# circuit_simplified.net
KiCad netlist of a schematic drawn in EAGLE
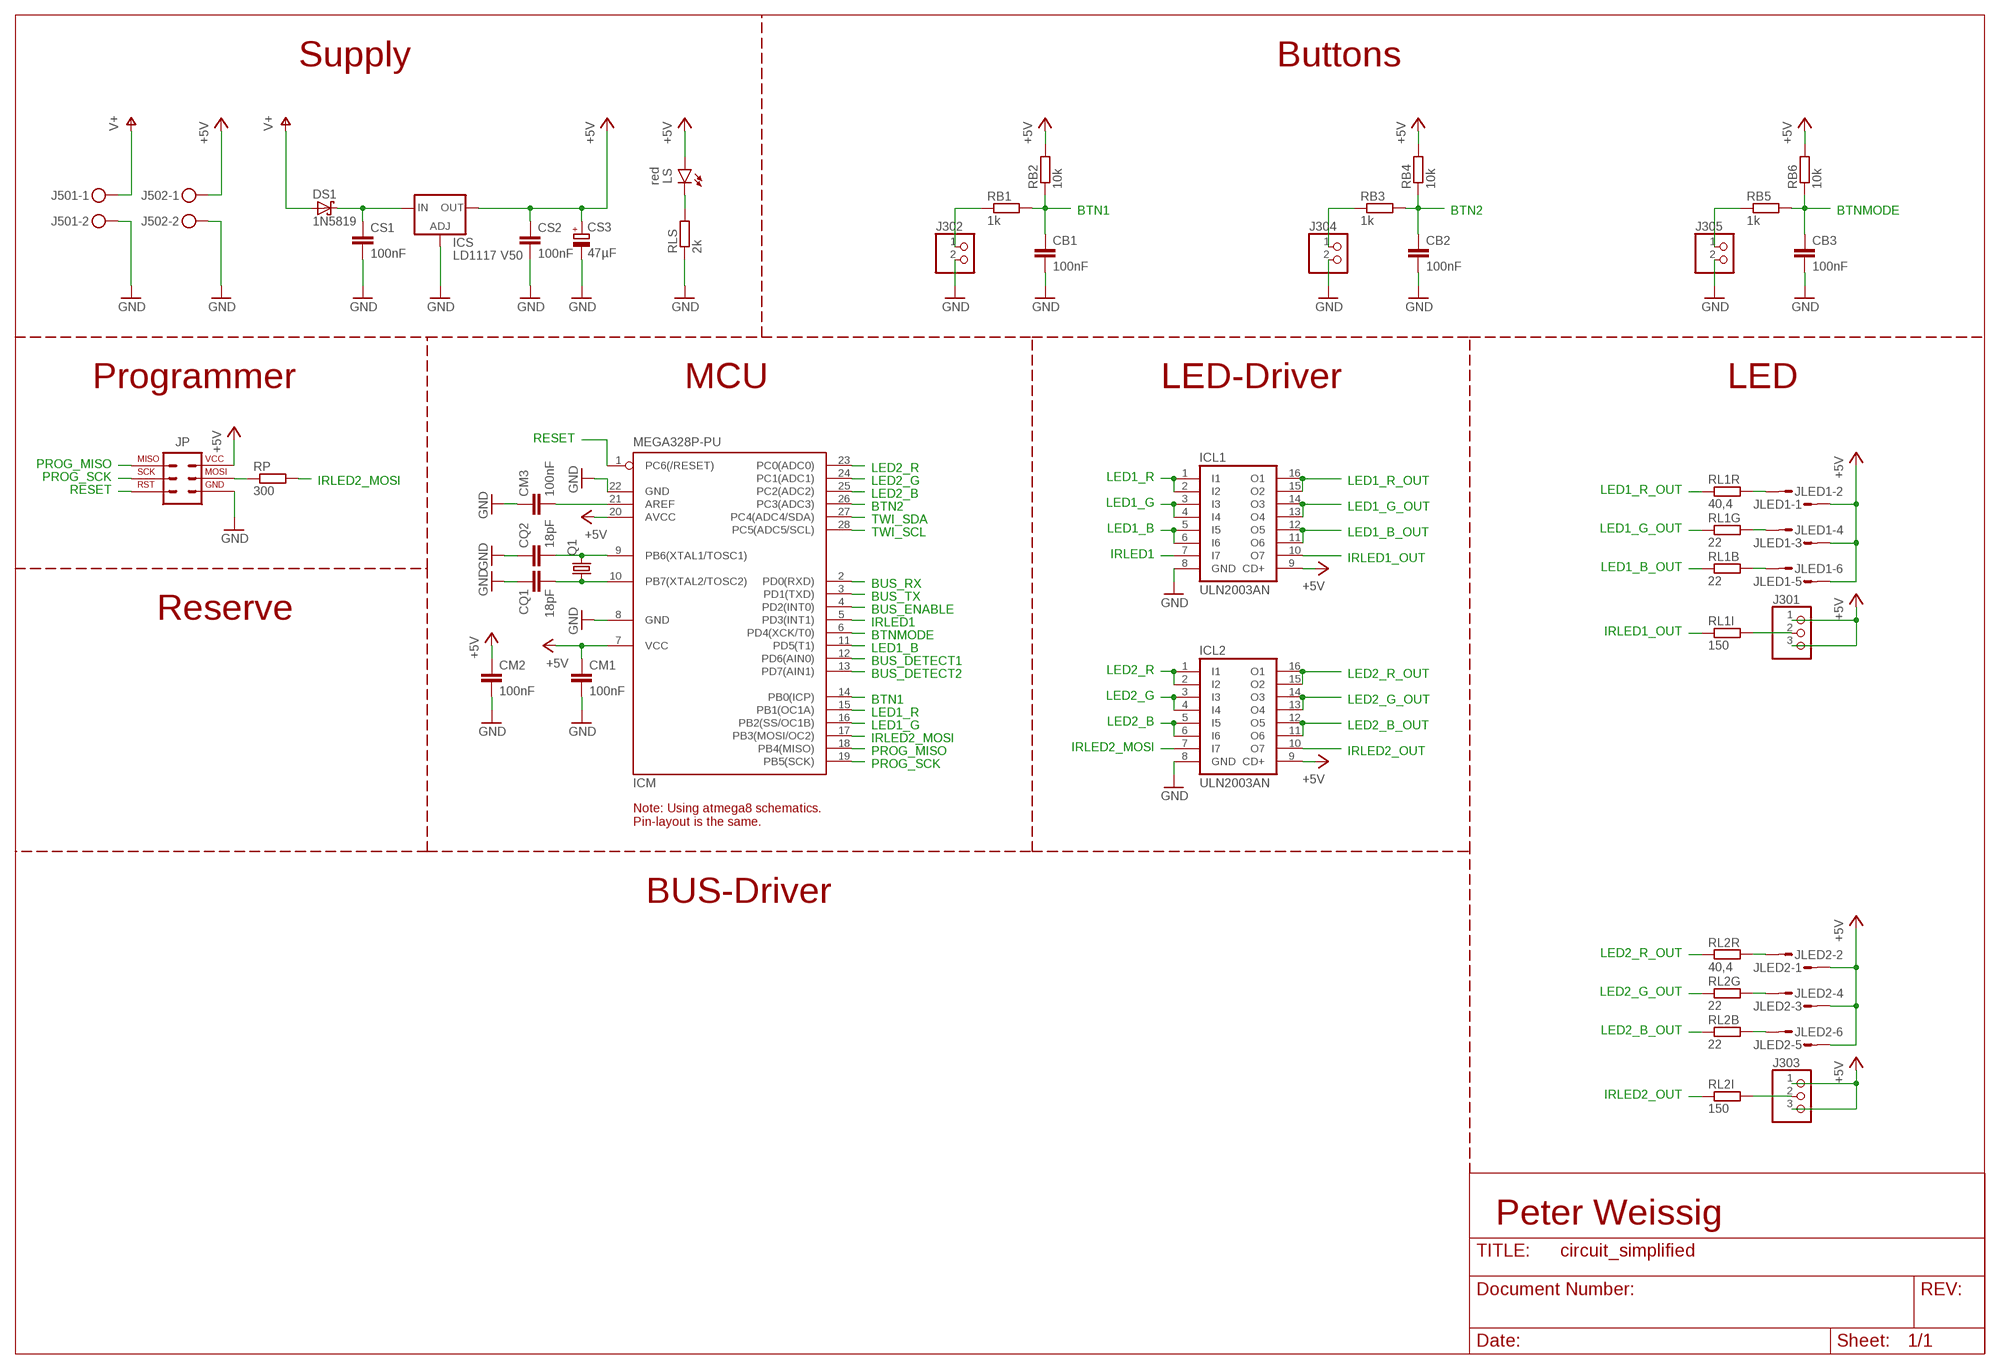
[diagram p0: schematic, sheet 1]

(export (version "E")
  (design (tool "Eeschema 10.0.6"))
  (components
    (comp (ref "CB1")
      (value "100nF")
      (footprint "eagle-import:C025-025X050")
      (libsource (lib "eagle-import") (part "C-EU025-025X050"))
    )
    (comp (ref "CB2")
      (value "100nF")
      (footprint "eagle-import:C025-025X050")
      (libsource (lib "eagle-import") (part "C-EU025-025X050"))
    )
    (comp (ref "CB3")
      (value "100nF")
      (footprint "eagle-import:C025-025X050")
      (libsource (lib "eagle-import") (part "C-EU025-025X050"))
    )
    (comp (ref "CM1")
      (value "100nF")
      (footprint "eagle-import:C025-025X050")
      (libsource (lib "eagle-import") (part "C-EU025-025X050"))
    )
    (comp (ref "CM2")
      (value "100nF")
      (footprint "eagle-import:C025-025X050")
      (libsource (lib "eagle-import") (part "C-EU025-025X050"))
    )
    (comp (ref "CM3")
      (value "100nF")
      (footprint "eagle-import:C025-025X050")
      (libsource (lib "eagle-import") (part "C-EU025-025X050"))
    )
    (comp (ref "CQ1")
      (value "18pF")
      (footprint "eagle-import:C025-025X050")
      (libsource (lib "eagle-import") (part "C-EU025-025X050"))
    )
    (comp (ref "CQ2")
      (value "18pF")
      (footprint "eagle-import:C025-025X050")
      (libsource (lib "eagle-import") (part "C-EU025-025X050"))
    )
    (comp (ref "CS1")
      (value "100nF")
      (footprint "eagle-import:C025-025X050")
      (libsource (lib "eagle-import") (part "C-EU025-025X050"))
    )
    (comp (ref "CS2")
      (value "100nF")
      (footprint "eagle-import:C025-025X050")
      (libsource (lib "eagle-import") (part "C-EU025-025X050"))
    )
    (comp (ref "CS3")
      (value "47µF")
      (footprint "eagle-import:E2-5")
      (libsource (lib "eagle-import") (part "CPOL-EUE2-5"))
    )
    (comp (ref "DS1")
      (value "1N5819")
      (footprint "eagle-import:DO41-7.6")
      (libsource (lib "eagle-import") (part "1N5819-B"))
    )
    (comp (ref "ICL1")
      (value "ULN2003AN")
      (footprint "eagle-import:DIL16")
      (libsource (lib "eagle-import") (part "ULN2003AN"))
    )
    (comp (ref "ICL2")
      (value "ULN2003AN")
      (footprint "eagle-import:DIL16")
      (libsource (lib "eagle-import") (part "ULN2003AN"))
    )
    (comp (ref "ICM")
      (value "MEGA328P-PU")
      (footprint "eagle-import:DIL28-3")
      (libsource (lib "eagle-import") (part "MEGA8-P"))
    )
    (comp (ref "ICS")
      (value "LD1117 V50")
      (footprint "eagle-import:TO220L1")
      (libsource (lib "eagle-import") (part "LD117A?V50"))
    )
    (comp (ref "J301")
      (value "PINHD-1X3")
      (footprint "eagle-import:1X03")
      (libsource (lib "eagle-import") (part "PINHD-1X3"))
    )
    (comp (ref "J302")
      (value "PINHD-1X2")
      (footprint "eagle-import:1X02")
      (libsource (lib "eagle-import") (part "PINHD-1X2"))
    )
    (comp (ref "J303")
      (value "PINHD-1X3")
      (footprint "eagle-import:1X03")
      (libsource (lib "eagle-import") (part "PINHD-1X3"))
    )
    (comp (ref "J304")
      (value "PINHD-1X2")
      (footprint "eagle-import:1X02")
      (libsource (lib "eagle-import") (part "PINHD-1X2"))
    )
    (comp (ref "J305")
      (value "PINHD-1X2")
      (footprint "eagle-import:1X02")
      (libsource (lib "eagle-import") (part "PINHD-1X2"))
    )
    (comp (ref "J501")
      (value "STECKER_SPG_2")
      (footprint "eagle-import:STECKER_SPG_2")
      (libsource (lib "eagle-import") (part "STECKER_SPG_2"))
    )
    (comp (ref "J502")
      (value "STECKER_SPG_2")
      (footprint "eagle-import:STECKER_SPG_2")
      (libsource (lib "eagle-import") (part "STECKER_SPG_2"))
    )
    (comp (ref "JLED1")
      (value "MICROMATCH-6")
      (footprint "eagle-import:MICROMATCH-6")
      (fields (field (name "MPN") "7-215464-6"))
      (libsource (lib "eagle-import") (part "MICROMATCH-6"))
    )
    (comp (ref "JLED2")
      (value "MICROMATCH-6")
      (footprint "eagle-import:MICROMATCH-6")
      (fields (field (name "MPN") "7-215464-6"))
      (libsource (lib "eagle-import") (part "MICROMATCH-6"))
    )
    (comp (ref "JP")
      (value "STECKER_ISP_6")
      (footprint "eagle-import:STECKER_WANNE_6")
      (libsource (lib "eagle-import") (part "STECKER_ISP_6"))
    )
    (comp (ref "LS")
      (value "red")
      (footprint "eagle-import:LED_3MM")
      (libsource (lib "eagle-import") (part "LED-3MM"))
    )
    (comp (ref "Q1")
      (value "CRYSTALHC49U70")
      (footprint "eagle-import:HC49U70")
      (libsource (lib "eagle-import") (part "CRYSTALHC49U70"))
    )
    (comp (ref "RB1")
      (value "1k")
      (footprint "eagle-import:0207_10")
      (libsource (lib "eagle-import") (part "R-EU_0207/10"))
    )
    (comp (ref "RB2")
      (value "10k")
      (footprint "eagle-import:0207_10")
      (libsource (lib "eagle-import") (part "R-EU_0207/10"))
    )
    (comp (ref "RB3")
      (value "1k")
      (footprint "eagle-import:0207_10")
      (libsource (lib "eagle-import") (part "R-EU_0207/10"))
    )
    (comp (ref "RB4")
      (value "10k")
      (footprint "eagle-import:0207_10")
      (libsource (lib "eagle-import") (part "R-EU_0207/10"))
    )
    (comp (ref "RB5")
      (value "1k")
      (footprint "eagle-import:0207_10")
      (libsource (lib "eagle-import") (part "R-EU_0207/10"))
    )
    (comp (ref "RB6")
      (value "10k")
      (footprint "eagle-import:0207_10")
      (libsource (lib "eagle-import") (part "R-EU_0207/10"))
    )
    (comp (ref "RL1B")
      (value "22")
      (footprint "eagle-import:0207_10")
      (libsource (lib "eagle-import") (part "R-EU_0207/10"))
    )
    (comp (ref "RL1G")
      (value "22")
      (footprint "eagle-import:0207_10")
      (libsource (lib "eagle-import") (part "R-EU_0207/10"))
    )
    (comp (ref "RL1I")
      (value "150")
      (footprint "eagle-import:0207_10")
      (libsource (lib "eagle-import") (part "R-EU_0207/10"))
    )
    (comp (ref "RL1R")
      (value "40,4")
      (footprint "eagle-import:0207_10")
      (libsource (lib "eagle-import") (part "R-EU_0207/10"))
    )
    (comp (ref "RL2B")
      (value "22")
      (footprint "eagle-import:0207_10")
      (libsource (lib "eagle-import") (part "R-EU_0207/10"))
    )
    (comp (ref "RL2G")
      (value "22")
      (footprint "eagle-import:0207_10")
      (libsource (lib "eagle-import") (part "R-EU_0207/10"))
    )
    (comp (ref "RL2I")
      (value "150")
      (footprint "eagle-import:0207_10")
      (libsource (lib "eagle-import") (part "R-EU_0207/10"))
    )
    (comp (ref "RL2R")
      (value "40,4")
      (footprint "eagle-import:0207_10")
      (libsource (lib "eagle-import") (part "R-EU_0207/10"))
    )
    (comp (ref "RLS")
      (value "2k")
      (footprint "eagle-import:0207_10")
      (libsource (lib "eagle-import") (part "R-EU_0207/10"))
    )
    (comp (ref "RP")
      (value "300")
      (footprint "eagle-import:0207_10")
      (libsource (lib "eagle-import") (part "R-EU_0207/10"))
    )
  )
  (nets
    (net (code "1") (name "+5V") (class "Default")
      (node (ref "CM1") (pin "1") (pinfunction "1_1") (pintype "passive"))
      (node (ref "CM2") (pin "1") (pinfunction "1_1") (pintype "passive"))
      (node (ref "CS2") (pin "1") (pinfunction "1_1") (pintype "passive"))
      (node (ref "CS3") (pin "+") (pinfunction "+_+") (pintype "passive"))
      (node (ref "ICL1") (pin "9") (pinfunction "CD+_9") (pintype "passive"))
      (node (ref "ICL2") (pin "9") (pinfunction "CD+_9") (pintype "passive"))
      (node (ref "ICM") (pin "20") (pinfunction "AVCC_20") (pintype "power_in"))
      (node (ref "ICM") (pin "7") (pinfunction "VCC_7") (pintype "power_in"))
      (node (ref "ICS") (pin "2") (pinfunction "OUT_2") (pintype "passive"))
      (node (ref "J301") (pin "1") (pinfunction "1_1") (pintype "passive"))
      (node (ref "J301") (pin "3") (pinfunction "3_3") (pintype "passive"))
      (node (ref "J303") (pin "1") (pinfunction "1_1") (pintype "passive"))
      (node (ref "J303") (pin "3") (pinfunction "3_3") (pintype "passive"))
      (node (ref "J502") (pin "1") (pinfunction "KL_1") (pintype "passive"))
      (node (ref "JLED1") (pin "1") (pinfunction "S_1") (pintype "passive"))
      (node (ref "JLED1") (pin "3") (pinfunction "S_3") (pintype "passive"))
      (node (ref "JLED1") (pin "5") (pinfunction "S_5") (pintype "passive"))
      (node (ref "JLED2") (pin "1") (pinfunction "S_1") (pintype "passive"))
      (node (ref "JLED2") (pin "3") (pinfunction "S_3") (pintype "passive"))
      (node (ref "JLED2") (pin "5") (pinfunction "S_5") (pintype "passive"))
      (node (ref "JP") (pin "2") (pinfunction "2_VCC_2") (pintype "passive"))
      (node (ref "LS") (pin "A") (pinfunction "A_A") (pintype "passive"))
      (node (ref "RB2") (pin "2") (pinfunction "2_2") (pintype "passive"))
      (node (ref "RB4") (pin "2") (pinfunction "2_2") (pintype "passive"))
      (node (ref "RB6") (pin "2") (pinfunction "2_2") (pintype "passive"))
    )
    (net (code "2") (name "/BTN1") (class "Default")
      (node (ref "CB1") (pin "1") (pinfunction "1_1") (pintype "passive"))
      (node (ref "ICM") (pin "14") (pinfunction "PB0(ICP)_14") (pintype "bidirectional"))
      (node (ref "RB1") (pin "2") (pinfunction "2_2") (pintype "passive"))
      (node (ref "RB2") (pin "1") (pinfunction "1_1") (pintype "passive"))
    )
    (net (code "3") (name "/BTN2") (class "Default")
      (node (ref "CB2") (pin "1") (pinfunction "1_1") (pintype "passive"))
      (node (ref "ICM") (pin "26") (pinfunction "PC3(ADC3)_26") (pintype "bidirectional"))
      (node (ref "RB3") (pin "2") (pinfunction "2_2") (pintype "passive"))
      (node (ref "RB4") (pin "1") (pinfunction "1_1") (pintype "passive"))
    )
    (net (code "4") (name "/BTNMODE") (class "Default")
      (node (ref "CB3") (pin "1") (pinfunction "1_1") (pintype "passive"))
      (node (ref "ICM") (pin "6") (pinfunction "PD4(XCK/T0)_6") (pintype "bidirectional"))
      (node (ref "RB5") (pin "2") (pinfunction "2_2") (pintype "passive"))
      (node (ref "RB6") (pin "1") (pinfunction "1_1") (pintype "passive"))
    )
    (net (code "5") (name "/BUS_DETECT1") (class "Default")
      (node (ref "ICM") (pin "12") (pinfunction "PD6(AIN0)_12") (pintype "bidirectional"))
    )
    (net (code "6") (name "/BUS_DETECT2") (class "Default")
      (node (ref "ICM") (pin "13") (pinfunction "PD7(AIN1)_13") (pintype "bidirectional"))
    )
    (net (code "7") (name "/BUS_ENABLE") (class "Default")
      (node (ref "ICM") (pin "4") (pinfunction "PD2(INT0)_4") (pintype "bidirectional"))
    )
    (net (code "8") (name "/BUS_RX") (class "Default")
      (node (ref "ICM") (pin "2") (pinfunction "PD0(RXD)_2") (pintype "bidirectional"))
    )
    (net (code "9") (name "/BUS_TX") (class "Default")
      (node (ref "ICM") (pin "3") (pinfunction "PD1(TXD)_3") (pintype "bidirectional"))
    )
    (net (code "10") (name "/IRLED1") (class "Default")
      (node (ref "ICL1") (pin "7") (pinfunction "I7_7") (pintype "input"))
      (node (ref "ICM") (pin "5") (pinfunction "PD3(INT1)_5") (pintype "bidirectional"))
    )
    (net (code "11") (name "/IRLED1_OUT") (class "Default")
      (node (ref "ICL1") (pin "10") (pinfunction "O7_10") (pintype "open_collector"))
      (node (ref "RL1I") (pin "1") (pinfunction "1_1") (pintype "passive"))
    )
    (net (code "12") (name "/IRLED2_MOSI") (class "Default")
      (node (ref "ICL2") (pin "7") (pinfunction "I7_7") (pintype "input"))
      (node (ref "ICM") (pin "17") (pinfunction "PB3(MOSI/OC2)_17") (pintype "bidirectional"))
      (node (ref "RP") (pin "2") (pinfunction "2_2") (pintype "passive"))
    )
    (net (code "13") (name "/IRLED2_OUT") (class "Default")
      (node (ref "ICL2") (pin "10") (pinfunction "O7_10") (pintype "open_collector"))
      (node (ref "RL2I") (pin "1") (pinfunction "1_1") (pintype "passive"))
    )
    (net (code "14") (name "/LED1_B") (class "Default")
      (node (ref "ICL1") (pin "5") (pinfunction "I5_5") (pintype "input"))
      (node (ref "ICL1") (pin "6") (pinfunction "I6_6") (pintype "input"))
      (node (ref "ICM") (pin "11") (pinfunction "PD5(T1)_11") (pintype "bidirectional"))
    )
    (net (code "15") (name "/LED1_B_OUT") (class "Default")
      (node (ref "ICL1") (pin "11") (pinfunction "O6_11") (pintype "open_collector"))
      (node (ref "ICL1") (pin "12") (pinfunction "O5_12") (pintype "open_collector"))
      (node (ref "RL1B") (pin "1") (pinfunction "1_1") (pintype "passive"))
    )
    (net (code "16") (name "/LED1_G") (class "Default")
      (node (ref "ICL1") (pin "3") (pinfunction "I3_3") (pintype "input"))
      (node (ref "ICL1") (pin "4") (pinfunction "I4_4") (pintype "input"))
      (node (ref "ICM") (pin "16") (pinfunction "PB2(SS/OC1B)_16") (pintype "bidirectional"))
    )
    (net (code "17") (name "/LED1_G_OUT") (class "Default")
      (node (ref "ICL1") (pin "13") (pinfunction "O4_13") (pintype "open_collector"))
      (node (ref "ICL1") (pin "14") (pinfunction "O3_14") (pintype "open_collector"))
      (node (ref "RL1G") (pin "1") (pinfunction "1_1") (pintype "passive"))
    )
    (net (code "18") (name "/LED1_R") (class "Default")
      (node (ref "ICL1") (pin "1") (pinfunction "I1_1") (pintype "input"))
      (node (ref "ICL1") (pin "2") (pinfunction "I2_2") (pintype "input"))
      (node (ref "ICM") (pin "15") (pinfunction "PB1(OC1A)_15") (pintype "bidirectional"))
    )
    (net (code "19") (name "/LED1_R_OUT") (class "Default")
      (node (ref "ICL1") (pin "15") (pinfunction "O2_15") (pintype "open_collector"))
      (node (ref "ICL1") (pin "16") (pinfunction "O1_16") (pintype "open_collector"))
      (node (ref "RL1R") (pin "1") (pinfunction "1_1") (pintype "passive"))
    )
    (net (code "20") (name "/LED2_B") (class "Default")
      (node (ref "ICL2") (pin "5") (pinfunction "I5_5") (pintype "input"))
      (node (ref "ICL2") (pin "6") (pinfunction "I6_6") (pintype "input"))
      (node (ref "ICM") (pin "25") (pinfunction "PC2(ADC2)_25") (pintype "bidirectional"))
    )
    (net (code "21") (name "/LED2_B_OUT") (class "Default")
      (node (ref "ICL2") (pin "11") (pinfunction "O6_11") (pintype "open_collector"))
      (node (ref "ICL2") (pin "12") (pinfunction "O5_12") (pintype "open_collector"))
      (node (ref "RL2B") (pin "1") (pinfunction "1_1") (pintype "passive"))
    )
    (net (code "22") (name "/LED2_G") (class "Default")
      (node (ref "ICL2") (pin "3") (pinfunction "I3_3") (pintype "input"))
      (node (ref "ICL2") (pin "4") (pinfunction "I4_4") (pintype "input"))
      (node (ref "ICM") (pin "24") (pinfunction "PC1(ADC1)_24") (pintype "bidirectional"))
    )
    (net (code "23") (name "/LED2_G_OUT") (class "Default")
      (node (ref "ICL2") (pin "13") (pinfunction "O4_13") (pintype "open_collector"))
      (node (ref "ICL2") (pin "14") (pinfunction "O3_14") (pintype "open_collector"))
      (node (ref "RL2G") (pin "1") (pinfunction "1_1") (pintype "passive"))
    )
    (net (code "24") (name "/LED2_R") (class "Default")
      (node (ref "ICL2") (pin "1") (pinfunction "I1_1") (pintype "input"))
      (node (ref "ICL2") (pin "2") (pinfunction "I2_2") (pintype "input"))
      (node (ref "ICM") (pin "23") (pinfunction "PC0(ADC0)_23") (pintype "bidirectional"))
    )
    (net (code "25") (name "/LED2_R_OUT") (class "Default")
      (node (ref "ICL2") (pin "15") (pinfunction "O2_15") (pintype "open_collector"))
      (node (ref "ICL2") (pin "16") (pinfunction "O1_16") (pintype "open_collector"))
      (node (ref "RL2R") (pin "1") (pinfunction "1_1") (pintype "passive"))
    )
    (net (code "26") (name "/PROG_MISO") (class "Default")
      (node (ref "ICM") (pin "18") (pinfunction "PB4(MISO)_18") (pintype "bidirectional"))
      (node (ref "JP") (pin "1") (pinfunction "1_MISO_1") (pintype "passive"))
    )
    (net (code "27") (name "/PROG_SCK") (class "Default")
      (node (ref "ICM") (pin "19") (pinfunction "PB5(SCK)_19") (pintype "bidirectional"))
      (node (ref "JP") (pin "3") (pinfunction "3_SCK_3") (pintype "passive"))
    )
    (net (code "28") (name "/RESET") (class "Default")
      (node (ref "ICM") (pin "1") (pinfunction "PC6(/RESET)_1") (pintype "bidirectional"))
      (node (ref "JP") (pin "5") (pinfunction "5_RST_5") (pintype "passive"))
    )
    (net (code "29") (name "/TWI_SCL") (class "Default")
      (node (ref "ICM") (pin "28") (pinfunction "PC5(ADC5/SCL)_28") (pintype "bidirectional"))
    )
    (net (code "30") (name "/TWI_SDA") (class "Default")
      (node (ref "ICM") (pin "27") (pinfunction "PC4(ADC4/SDA)_27") (pintype "bidirectional"))
    )
    (net (code "31") (name "GND") (class "Default")
      (node (ref "CB1") (pin "2") (pinfunction "2_2") (pintype "passive"))
      (node (ref "CB2") (pin "2") (pinfunction "2_2") (pintype "passive"))
      (node (ref "CB3") (pin "2") (pinfunction "2_2") (pintype "passive"))
      (node (ref "CM1") (pin "2") (pinfunction "2_2") (pintype "passive"))
      (node (ref "CM2") (pin "2") (pinfunction "2_2") (pintype "passive"))
      (node (ref "CM3") (pin "1") (pinfunction "1_1") (pintype "passive"))
      (node (ref "CQ1") (pin "1") (pinfunction "1_1") (pintype "passive"))
      (node (ref "CQ2") (pin "1") (pinfunction "1_1") (pintype "passive"))
      (node (ref "CS1") (pin "2") (pinfunction "2_2") (pintype "passive"))
      (node (ref "CS2") (pin "2") (pinfunction "2_2") (pintype "passive"))
      (node (ref "CS3") (pin "-") (pinfunction "-_-") (pintype "passive"))
      (node (ref "ICL1") (pin "8") (pinfunction "GND_8") (pintype "power_in"))
      (node (ref "ICL2") (pin "8") (pinfunction "GND_8") (pintype "power_in"))
      (node (ref "ICM") (pin "22") (pinfunction "GND_22") (pintype "power_in"))
      (node (ref "ICM") (pin "8") (pinfunction "GND_8") (pintype "power_in"))
      (node (ref "ICS") (pin "1") (pinfunction "ADJ_1") (pintype "input"))
      (node (ref "J302") (pin "2") (pinfunction "2_2") (pintype "passive"))
      (node (ref "J304") (pin "2") (pinfunction "2_2") (pintype "passive"))
      (node (ref "J305") (pin "2") (pinfunction "2_2") (pintype "passive"))
      (node (ref "J501") (pin "2") (pinfunction "KL_2") (pintype "passive"))
      (node (ref "J502") (pin "2") (pinfunction "KL_2") (pintype "passive"))
      (node (ref "JP") (pin "6") (pinfunction "6_GND_6") (pintype "passive"))
      (node (ref "RLS") (pin "1") (pinfunction "1_1") (pintype "passive"))
    )
    (net (code "32") (name "Net-(ICM-AREF)") (class "Default")
      (node (ref "CM3") (pin "2") (pinfunction "2_2") (pintype "passive"))
      (node (ref "ICM") (pin "21") (pinfunction "AREF_21") (pintype "passive"))
    )
    (net (code "33") (name "Net-(ICM-PB6(XTAL1{slash}TOSC1))") (class "Default")
      (node (ref "CQ2") (pin "2") (pinfunction "2_2") (pintype "passive"))
      (node (ref "ICM") (pin "9") (pinfunction "PB6(XTAL1/TOSC1)_9") (pintype "bidirectional"))
      (node (ref "Q1") (pin "2") (pinfunction "2_2") (pintype "passive"))
    )
    (net (code "34") (name "Net-(ICM-PB7(XTAL2{slash}TOSC2))") (class "Default")
      (node (ref "CQ1") (pin "2") (pinfunction "2_2") (pintype "passive"))
      (node (ref "ICM") (pin "10") (pinfunction "PB7(XTAL2/TOSC2)_10") (pintype "bidirectional"))
      (node (ref "Q1") (pin "1") (pinfunction "1_1") (pintype "passive"))
    )
    (net (code "35") (name "Net-(ICS-IN)") (class "Default")
      (node (ref "CS1") (pin "1") (pinfunction "1_1") (pintype "passive"))
      (node (ref "DS1") (pin "C") (pinfunction "C_C") (pintype "passive"))
      (node (ref "ICS") (pin "3") (pinfunction "IN_3") (pintype "input"))
    )
    (net (code "36") (name "Net-(J301-Pad2)") (class "Default")
      (node (ref "J301") (pin "2") (pinfunction "2_2") (pintype "passive"))
      (node (ref "RL1I") (pin "2") (pinfunction "2_2") (pintype "passive"))
    )
    (net (code "37") (name "Net-(J302-Pad1)") (class "Default")
      (node (ref "J302") (pin "1") (pinfunction "1_1") (pintype "passive"))
      (node (ref "RB1") (pin "1") (pinfunction "1_1") (pintype "passive"))
    )
    (net (code "38") (name "Net-(J303-Pad2)") (class "Default")
      (node (ref "J303") (pin "2") (pinfunction "2_2") (pintype "passive"))
      (node (ref "RL2I") (pin "2") (pinfunction "2_2") (pintype "passive"))
    )
    (net (code "39") (name "Net-(J304-Pad1)") (class "Default")
      (node (ref "J304") (pin "1") (pinfunction "1_1") (pintype "passive"))
      (node (ref "RB3") (pin "1") (pinfunction "1_1") (pintype "passive"))
    )
    (net (code "40") (name "Net-(J305-Pad1)") (class "Default")
      (node (ref "J305") (pin "1") (pinfunction "1_1") (pintype "passive"))
      (node (ref "RB5") (pin "1") (pinfunction "1_1") (pintype "passive"))
    )
    (net (code "41") (name "Net-(JLED1B-S)") (class "Default")
      (node (ref "JLED1") (pin "2") (pinfunction "S_2") (pintype "passive"))
      (node (ref "RL1R") (pin "2") (pinfunction "2_2") (pintype "passive"))
    )
    (net (code "42") (name "Net-(JLED1D-S)") (class "Default")
      (node (ref "JLED1") (pin "4") (pinfunction "S_4") (pintype "passive"))
      (node (ref "RL1G") (pin "2") (pinfunction "2_2") (pintype "passive"))
    )
    (net (code "43") (name "Net-(JLED1F-S)") (class "Default")
      (node (ref "JLED1") (pin "6") (pinfunction "S_6") (pintype "passive"))
      (node (ref "RL1B") (pin "2") (pinfunction "2_2") (pintype "passive"))
    )
    (net (code "44") (name "Net-(JLED2B-S)") (class "Default")
      (node (ref "JLED2") (pin "2") (pinfunction "S_2") (pintype "passive"))
      (node (ref "RL2R") (pin "2") (pinfunction "2_2") (pintype "passive"))
    )
    (net (code "45") (name "Net-(JLED2D-S)") (class "Default")
      (node (ref "JLED2") (pin "4") (pinfunction "S_4") (pintype "passive"))
      (node (ref "RL2G") (pin "2") (pinfunction "2_2") (pintype "passive"))
    )
    (net (code "46") (name "Net-(JLED2F-S)") (class "Default")
      (node (ref "JLED2") (pin "6") (pinfunction "S_6") (pintype "passive"))
      (node (ref "RL2B") (pin "2") (pinfunction "2_2") (pintype "passive"))
    )
    (net (code "47") (name "Net-(JP-4_MOSI)") (class "Default")
      (node (ref "JP") (pin "4") (pinfunction "4_MOSI_4") (pintype "passive"))
      (node (ref "RP") (pin "1") (pinfunction "1_1") (pintype "passive"))
    )
    (net (code "48") (name "Net-(LS-C)") (class "Default")
      (node (ref "LS") (pin "K") (pinfunction "C_K") (pintype "passive"))
      (node (ref "RLS") (pin "2") (pinfunction "2_2") (pintype "passive"))
    )
    (net (code "49") (name "V+") (class "Default")
      (node (ref "DS1") (pin "A") (pinfunction "A_A") (pintype "passive"))
      (node (ref "J501") (pin "1") (pinfunction "KL_1") (pintype "passive"))
    )
  )
)
